# irdroid_secure.net
KiCad netlist of a schematic drawn in EAGLE
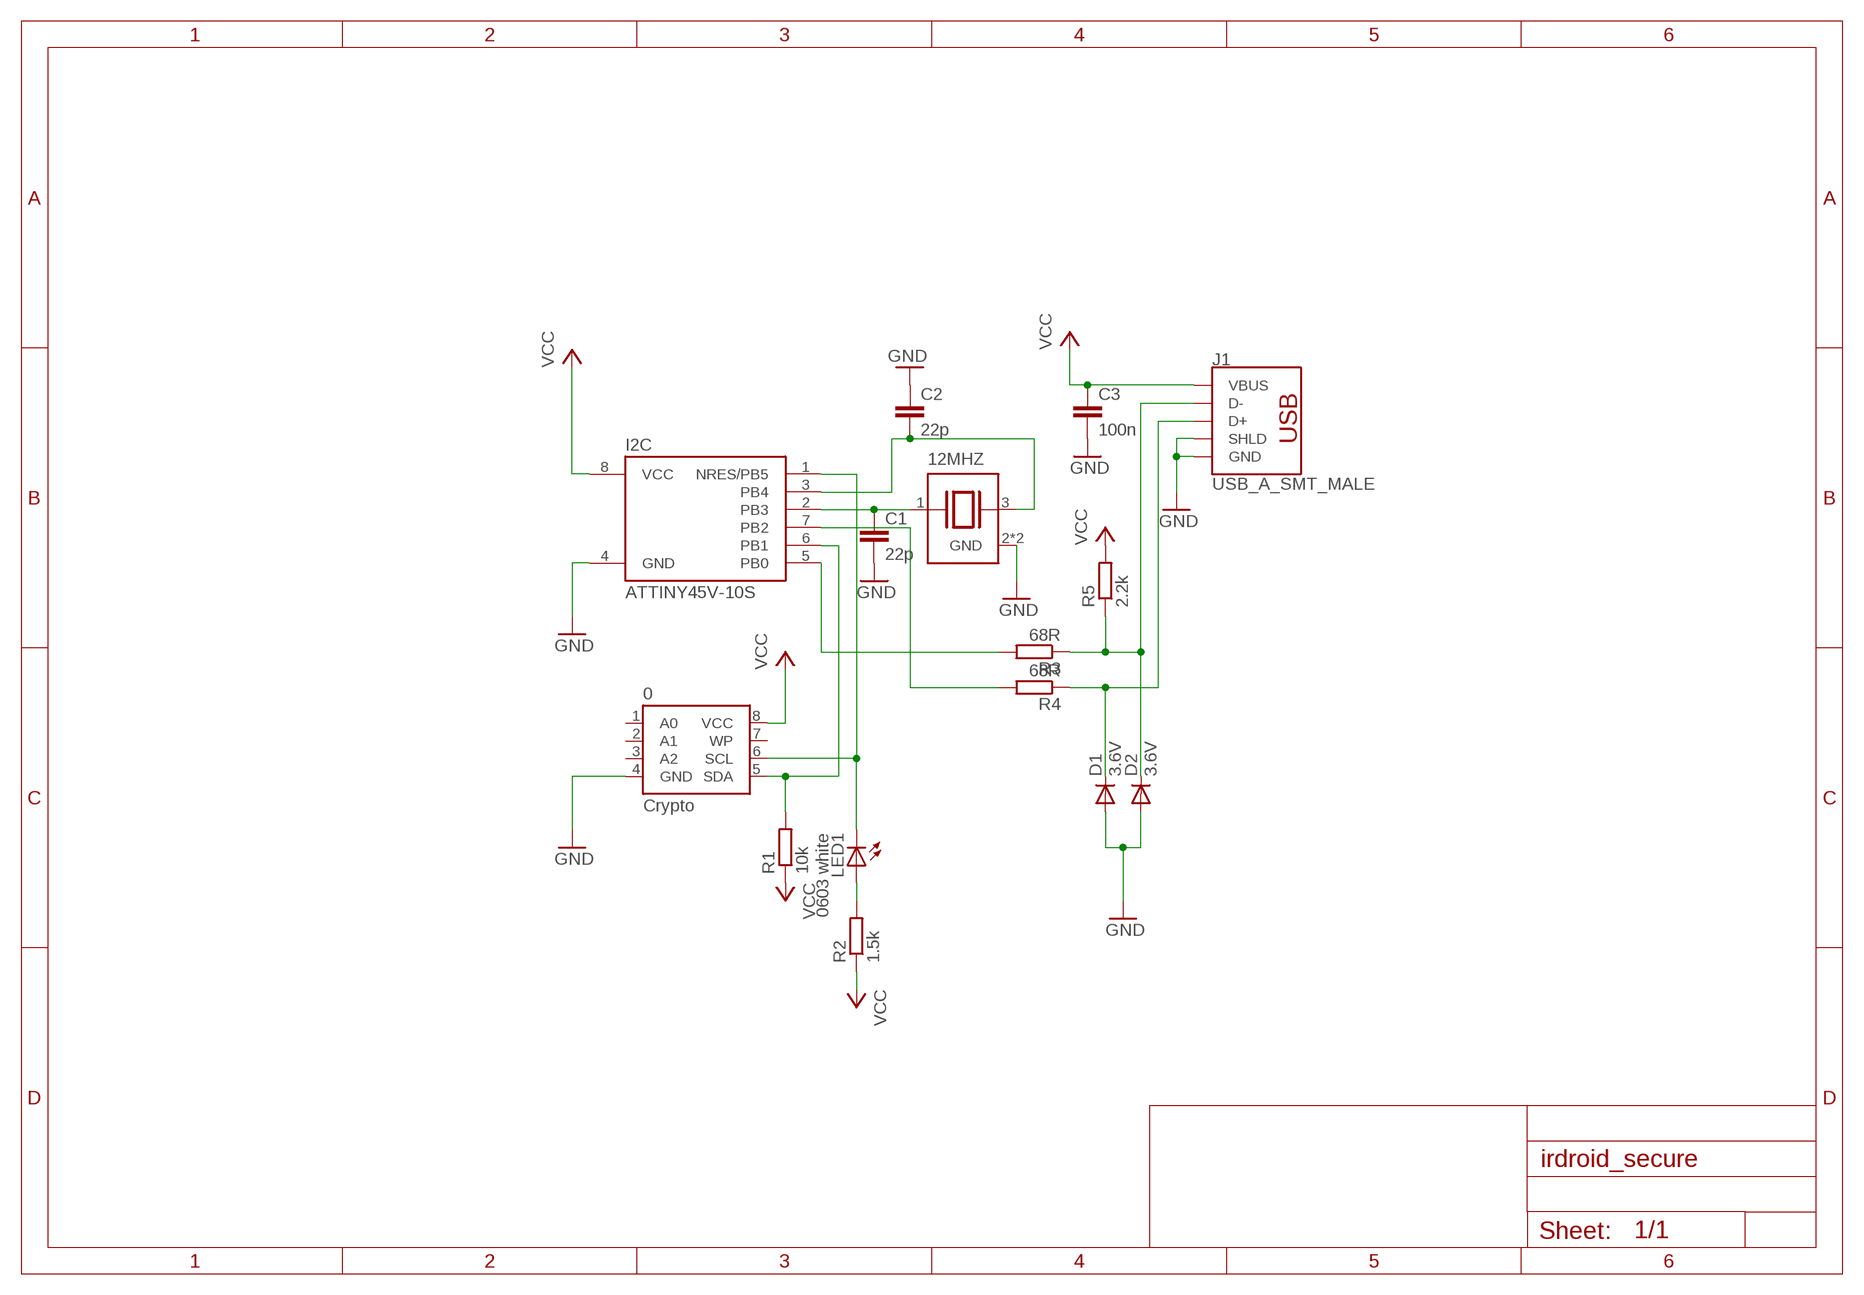
[diagram p0: schematic, sheet 1]

(export (version "E")
  (design (tool "Eeschema 10.0.6"))
  (components
    (comp (ref "0")
      (value "Crypto")
      (footprint "eagle-import:SO08")
      (libsource (lib "eagle-import") (part "EEPROM-I2C256K"))
    )
    (comp (ref "12MHZ")
      (value "ABM8-16.000MHZ-B2-T")
      (footprint "eagle-import:XTAL_ABM8-16.000MHZ-B2-T")
      (fields (field (name "MF") "Abracon"))
      (libsource (lib "eagle-import") (part "ABM8-16.000MHZ-B2-T"))
    )
    (comp (ref "C1")
      (value "22p")
      (footprint "eagle-import:C0603")
      (libsource (lib "eagle-import") (part "C-EUC0603"))
    )
    (comp (ref "C2")
      (value "22p")
      (footprint "eagle-import:C0603")
      (libsource (lib "eagle-import") (part "C-EUC0603"))
    )
    (comp (ref "C3")
      (value "100n")
      (footprint "eagle-import:C0603")
      (libsource (lib "eagle-import") (part "C-EUC0603"))
    )
    (comp (ref "D1")
      (value "3.6V")
      (footprint "eagle-import:SOD323-R")
      (libsource (lib "eagle-import") (part "DIODE-SOD323-R"))
    )
    (comp (ref "D2")
      (value "3.6V")
      (footprint "eagle-import:SOD323-R")
      (libsource (lib "eagle-import") (part "DIODE-SOD323-R"))
    )
    (comp (ref "I2C")
      (value "ATTINY45V-10S")
      (footprint "eagle-import:SOIC8_EIAJ_208MIL")
      (libsource (lib "eagle-import") (part "ATTINY45SV-10"))
    )
    (comp (ref "J1")
      (value "USB_A_SMT_MALE")
      (footprint "eagle-import:USB-A-SMT-MALE")
      (libsource (lib "eagle-import") (part "USB_A_SMT_MALE"))
    )
    (comp (ref "LED1")
      (value "0603 white")
      (footprint "eagle-import:CHIP-LED0603")
      (libsource (lib "eagle-import") (part "LEDCHIP-LED0603"))
    )
    (comp (ref "R1")
      (value "10k")
      (footprint "eagle-import:R0603")
      (libsource (lib "eagle-import") (part "R-EU_R0603"))
    )
    (comp (ref "R2")
      (value "1.5k")
      (footprint "eagle-import:R0603")
      (libsource (lib "eagle-import") (part "R-EU_R0603"))
    )
    (comp (ref "R3")
      (value "68R")
      (footprint "eagle-import:R0603")
      (libsource (lib "eagle-import") (part "R-EU_R0603"))
    )
    (comp (ref "R4")
      (value "68R")
      (footprint "eagle-import:R0603")
      (libsource (lib "eagle-import") (part "R-EU_R0603"))
    )
    (comp (ref "R5")
      (value "2.2k")
      (footprint "eagle-import:R0603")
      (libsource (lib "eagle-import") (part "R-EU_R0603"))
    )
  )
  (nets
    (net (code "1") (name "GND") (class "Default")
      (node (ref "0") (pin "4") (pinfunction "GND_4") (pintype "power_in"))
      (node (ref "12MHZ") (pin "2") (pinfunction "GND_2") (pintype "power_in"))
      (node (ref "12MHZ") (pin "4") (pinfunction "GND_4") (pintype "power_in"))
      (node (ref "C1") (pin "2") (pinfunction "2_2") (pintype "passive"))
      (node (ref "C2") (pin "1") (pinfunction "1_1") (pintype "passive"))
      (node (ref "C3") (pin "2") (pinfunction "2_2") (pintype "passive"))
      (node (ref "D1") (pin "A") (pinfunction "A_A") (pintype "passive"))
      (node (ref "D2") (pin "A") (pinfunction "A_A") (pintype "passive"))
      (node (ref "I2C") (pin "4") (pinfunction "GND_4") (pintype "power_in"))
      (node (ref "J1") (pin "GND1") (pinfunction "GND_GND1") (pintype "power_in"))
      (node (ref "J1") (pin "SHLD1") (pinfunction "SHLD_SHLD1") (pintype "bidirectional"))
      (node (ref "J1") (pin "SHLD2") (pinfunction "SHLD_SHLD2") (pintype "bidirectional"))
    )
    (net (code "2") (name "Net-(0-SCL)") (class "Default")
      (node (ref "0") (pin "6") (pinfunction "SCL_6") (pintype "bidirectional"))
      (node (ref "I2C") (pin "1") (pinfunction "NRES/PB5_1") (pintype "bidirectional"))
      (node (ref "LED1") (pin "C") (pinfunction "C_C") (pintype "passive"))
    )
    (net (code "3") (name "Net-(0-SDA)") (class "Default")
      (node (ref "0") (pin "5") (pinfunction "SDA_5") (pintype "bidirectional"))
      (node (ref "I2C") (pin "6") (pinfunction "PB1_6") (pintype "bidirectional"))
      (node (ref "R1") (pin "2") (pinfunction "2_2") (pintype "passive"))
    )
    (net (code "4") (name "Net-(12MHZ-2)") (class "Default")
      (node (ref "12MHZ") (pin "3") (pinfunction "2_3") (pintype "passive"))
      (node (ref "C2") (pin "2") (pinfunction "2_2") (pintype "passive"))
      (node (ref "I2C") (pin "3") (pinfunction "PB4_3") (pintype "bidirectional"))
    )
    (net (code "5") (name "Net-(I2C-PB0)") (class "Default")
      (node (ref "I2C") (pin "5") (pinfunction "PB0_5") (pintype "bidirectional"))
      (node (ref "R3") (pin "2") (pinfunction "2_2") (pintype "passive"))
    )
    (net (code "6") (name "Net-(I2C-PB2)") (class "Default")
      (node (ref "I2C") (pin "7") (pinfunction "PB2_7") (pintype "bidirectional"))
      (node (ref "R4") (pin "2") (pinfunction "2_2") (pintype "passive"))
    )
    (net (code "7") (name "Net-(I2C-PB3)") (class "Default")
      (node (ref "12MHZ") (pin "1") (pinfunction "1_1") (pintype "passive"))
      (node (ref "C1") (pin "1") (pinfunction "1_1") (pintype "passive"))
      (node (ref "I2C") (pin "2") (pinfunction "PB3_2") (pintype "bidirectional"))
    )
    (net (code "8") (name "Net-(J1-D+)") (class "Default")
      (node (ref "D1") (pin "C") (pinfunction "C_C") (pintype "passive"))
      (node (ref "J1") (pin "D+1") (pinfunction "D+_D+1") (pintype "bidirectional"))
      (node (ref "R4") (pin "1") (pinfunction "1_1") (pintype "passive"))
    )
    (net (code "9") (name "Net-(J1-D-)") (class "Default")
      (node (ref "D2") (pin "C") (pinfunction "C_C") (pintype "passive"))
      (node (ref "J1") (pin "D-1") (pinfunction "D-_D-1") (pintype "bidirectional"))
      (node (ref "R3") (pin "1") (pinfunction "1_1") (pintype "passive"))
      (node (ref "R5") (pin "1") (pinfunction "1_1") (pintype "passive"))
    )
    (net (code "10") (name "Net-(LED1-PadA)") (class "Default")
      (node (ref "LED1") (pin "A") (pinfunction "A_A") (pintype "passive"))
      (node (ref "R2") (pin "2") (pinfunction "2_2") (pintype "passive"))
    )
    (net (code "11") (name "VCC") (class "Default")
      (node (ref "0") (pin "8") (pinfunction "VCC_8") (pintype "power_in"))
      (node (ref "C3") (pin "1") (pinfunction "1_1") (pintype "passive"))
      (node (ref "I2C") (pin "8") (pinfunction "VCC_8") (pintype "power_in"))
      (node (ref "J1") (pin "VBUS1") (pinfunction "VBUS_VBUS1") (pintype "power_in"))
      (node (ref "R1") (pin "1") (pinfunction "1_1") (pintype "passive"))
      (node (ref "R2") (pin "1") (pinfunction "1_1") (pintype "passive"))
      (node (ref "R5") (pin "2") (pinfunction "2_2") (pintype "passive"))
    )
    (net (code "12") (name "unconnected-(0-A0-Pad1)") (class "Default")
      (node (ref "0") (pin "1") (pinfunction "A0_1") (pintype "bidirectional"))
    )
    (net (code "13") (name "unconnected-(0-A1-Pad2)") (class "Default")
      (node (ref "0") (pin "2") (pinfunction "A1_2") (pintype "bidirectional"))
    )
    (net (code "14") (name "unconnected-(0-A2-Pad3)") (class "Default")
      (node (ref "0") (pin "3") (pinfunction "A2_3") (pintype "bidirectional"))
    )
    (net (code "15") (name "unconnected-(0-WP-Pad7)") (class "Default")
      (node (ref "0") (pin "7") (pinfunction "WP_7") (pintype "bidirectional"))
    )
  )
)
